# imon.net
KiCad netlist of a schematic drawn in EAGLE
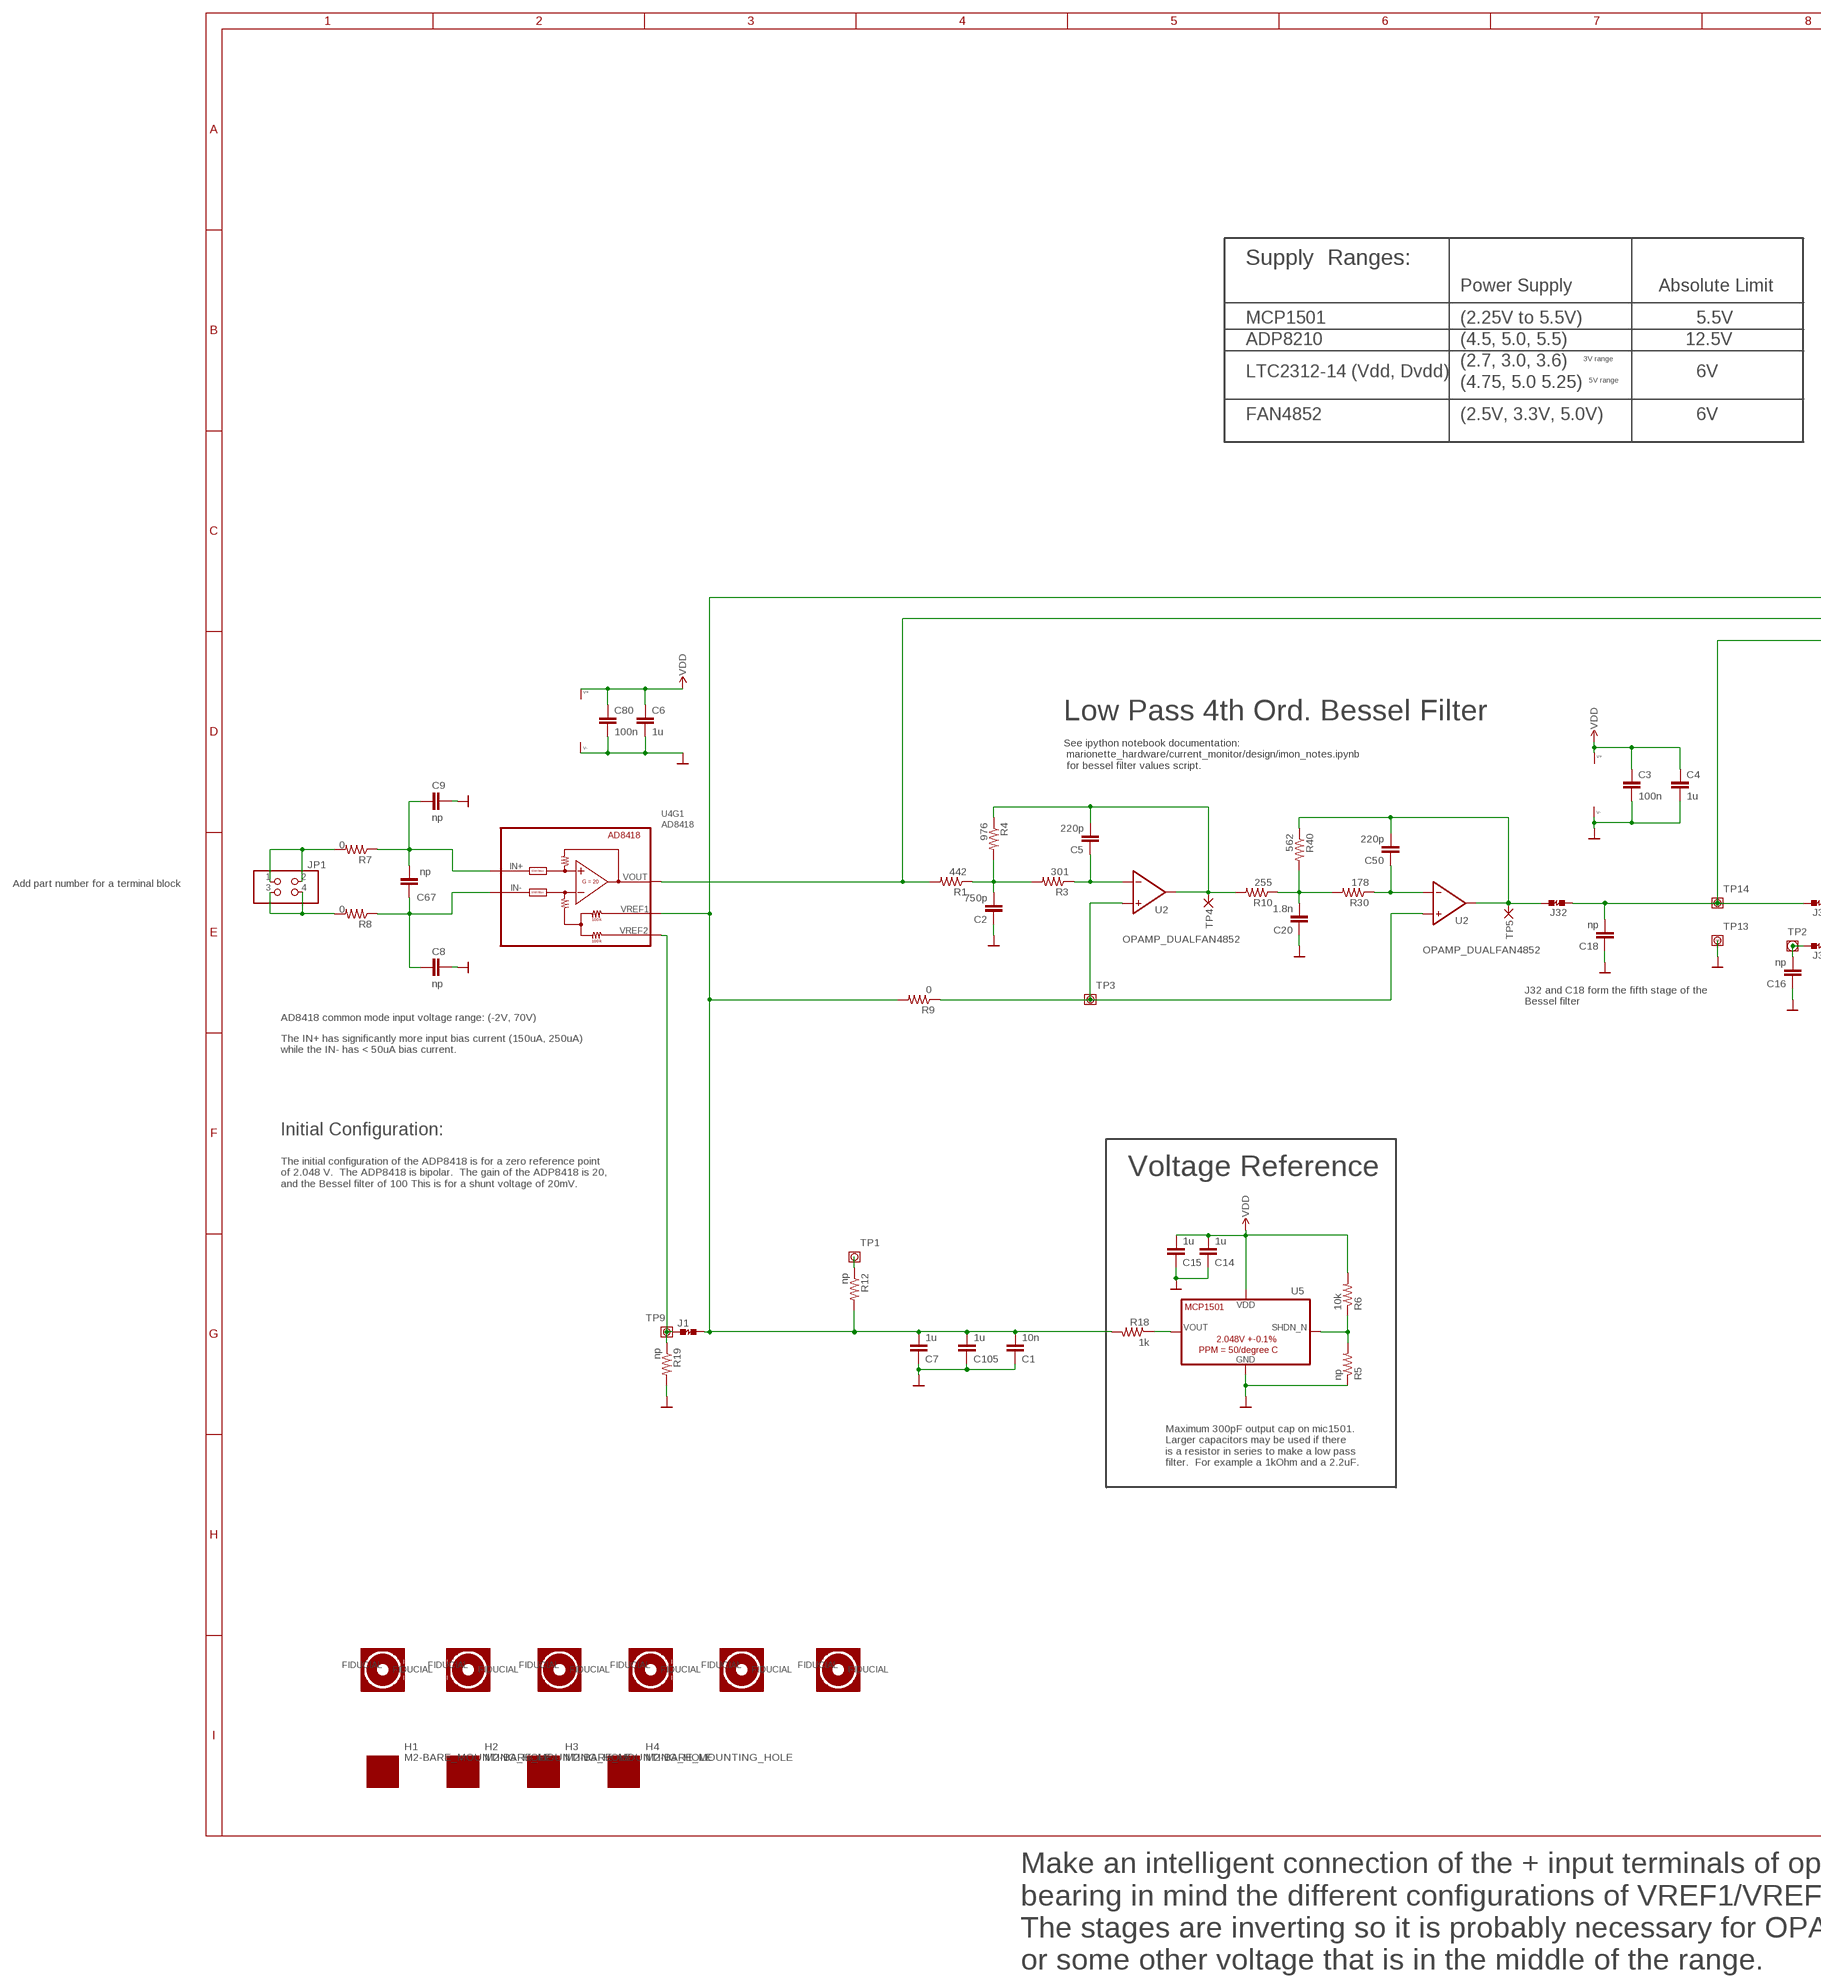
[diagram p0: schematic, sheet 1, part 1 of 2]
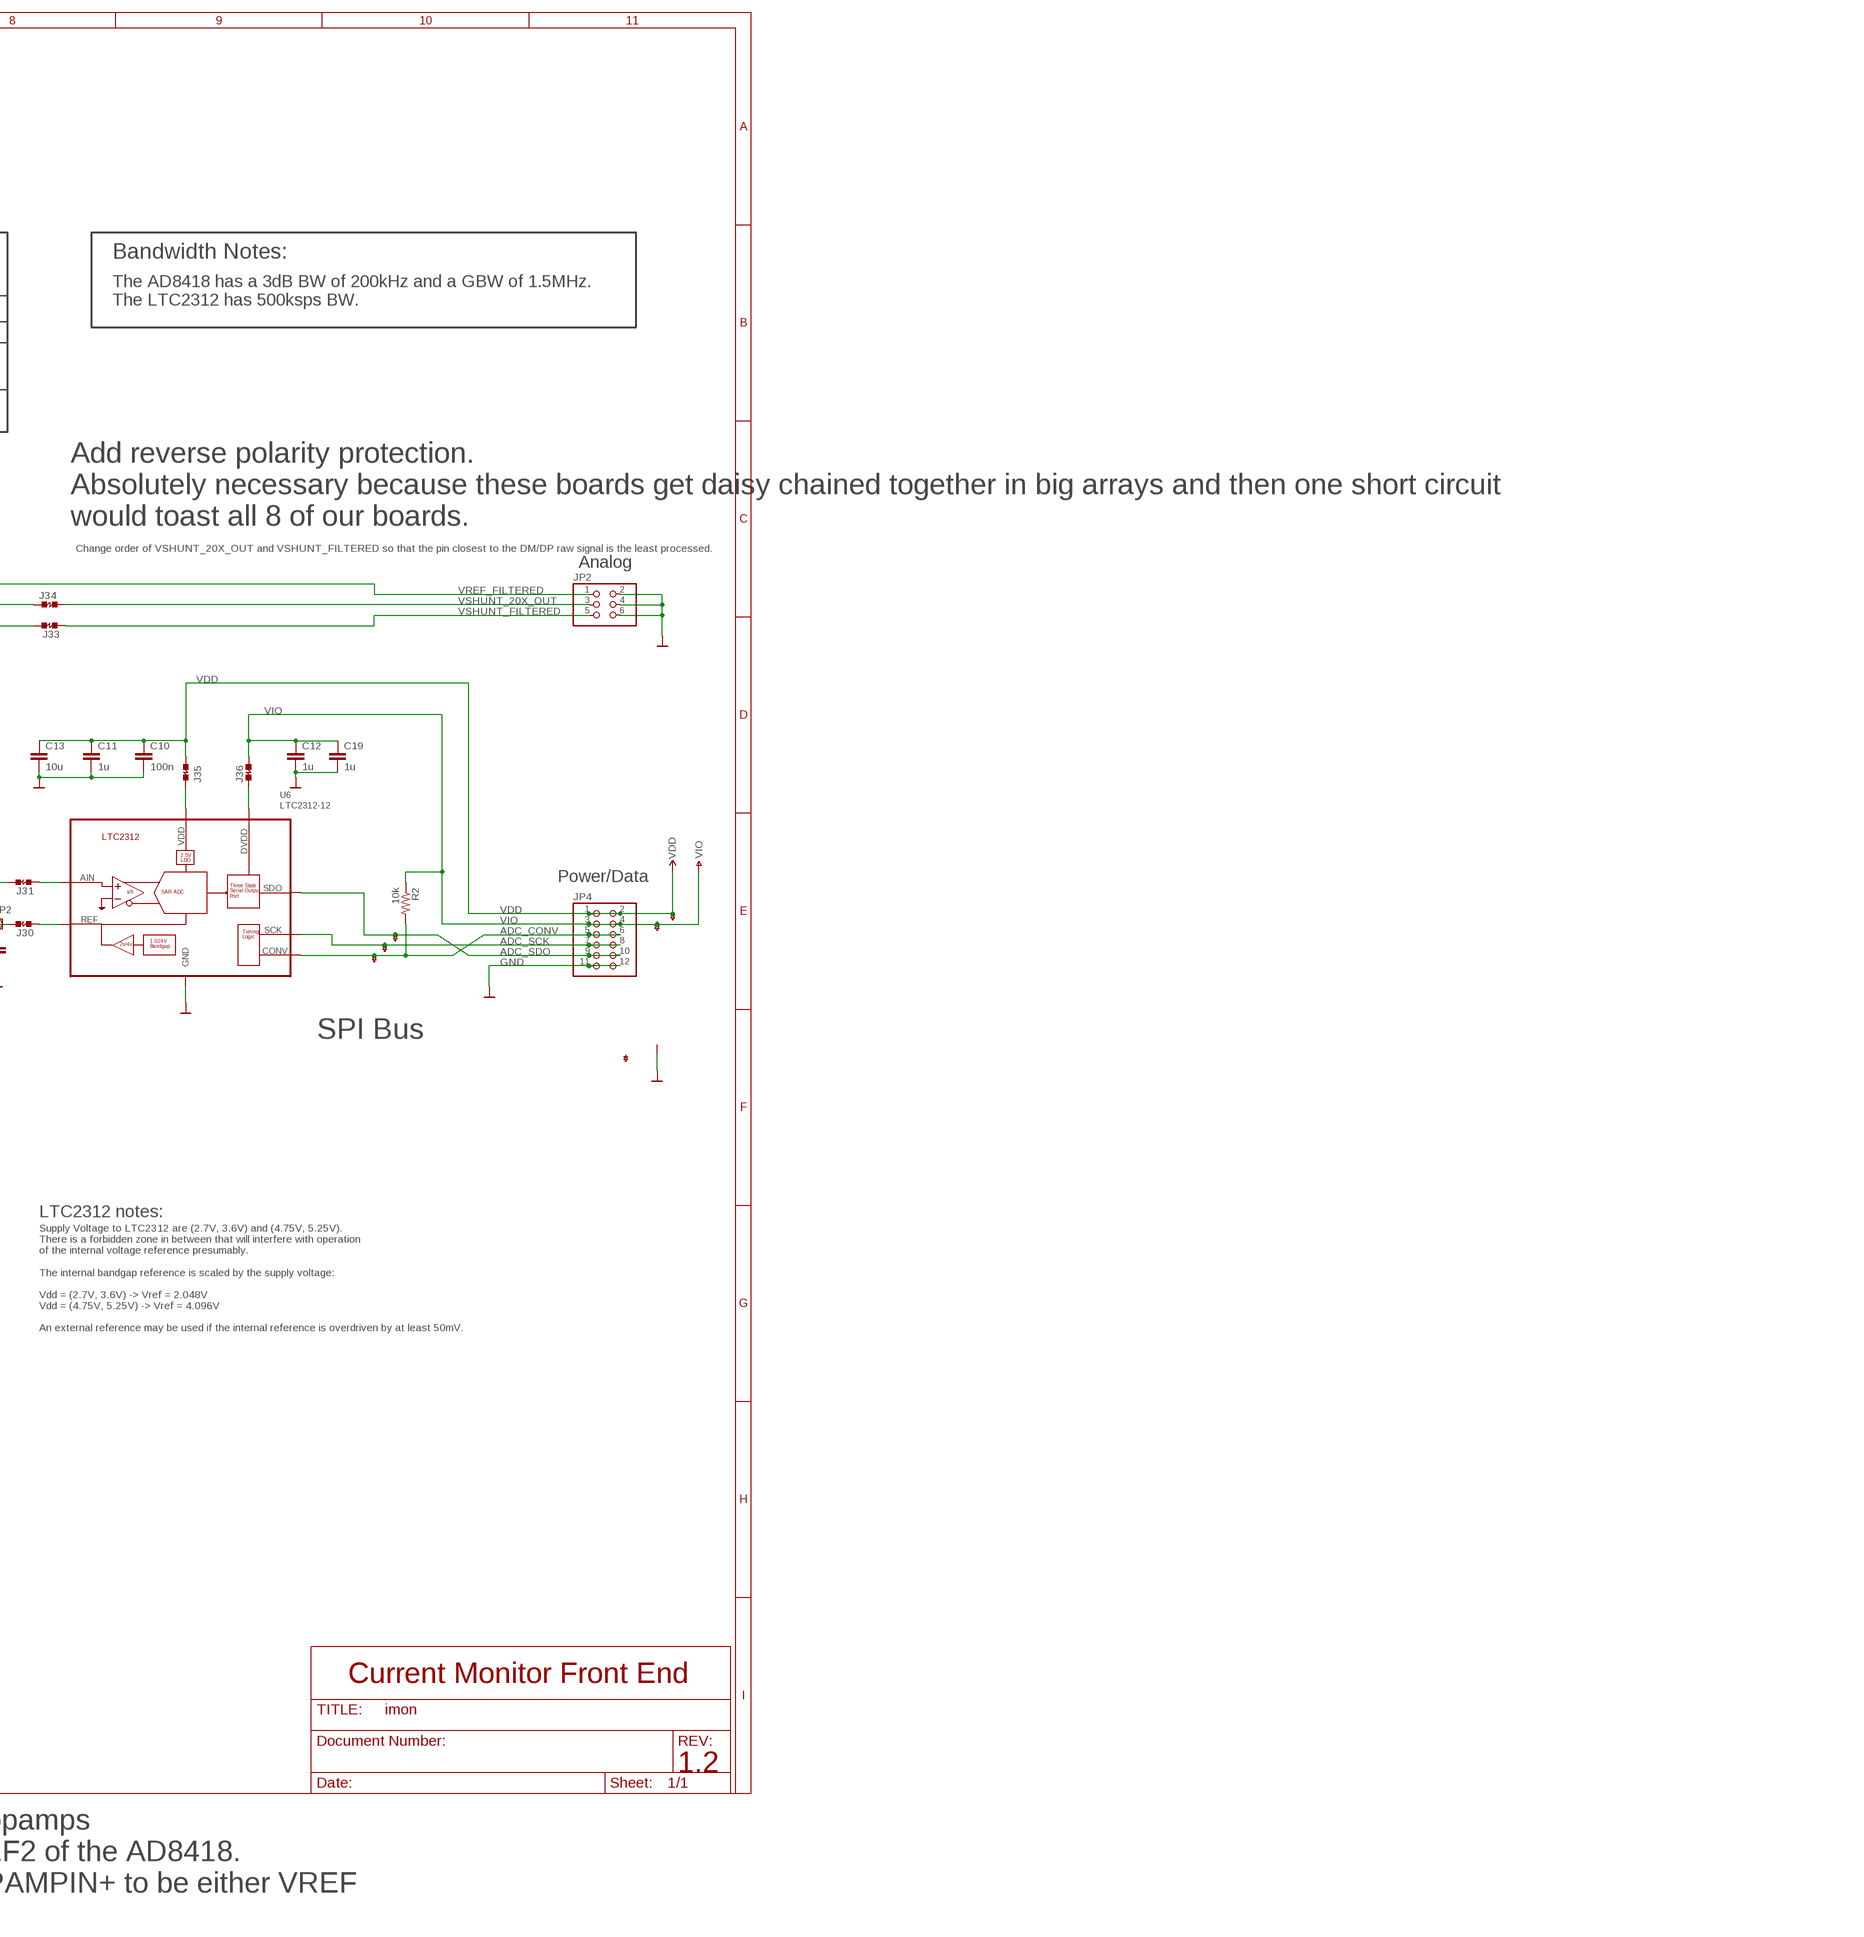
[diagram p1: schematic, sheet 1, part 2 of 2]

(export (version "E")
  (design (tool "Eeschema 10.0.6"))
  (components
    (comp (ref "C1")
      (value "10n")
      (footprint "eagle-import:.0402-B")
      (libsource (lib "eagle-import") (part "C-EU0402-B"))
    )
    (comp (ref "C2")
      (value "750p")
      (footprint "eagle-import:.0402-B")
      (libsource (lib "eagle-import") (part "C-EU0402-B"))
    )
    (comp (ref "C3")
      (value "100n")
      (footprint "eagle-import:.0402-B")
      (libsource (lib "eagle-import") (part "C-EU0402-B"))
    )
    (comp (ref "C4")
      (value "1u")
      (footprint "eagle-import:.0402-B")
      (libsource (lib "eagle-import") (part "C-EU0402-B"))
    )
    (comp (ref "C5")
      (value "220p")
      (footprint "eagle-import:.0402-B")
      (libsource (lib "eagle-import") (part "C-EU0402-B"))
    )
    (comp (ref "C6")
      (value "1u")
      (footprint "eagle-import:.0402-B")
      (libsource (lib "eagle-import") (part "C-EU0402-B"))
    )
    (comp (ref "C7")
      (value "1u")
      (footprint "eagle-import:.0402-B")
      (libsource (lib "eagle-import") (part "C-EU0402-B"))
    )
    (comp (ref "C8")
      (value "np")
      (footprint "eagle-import:.0805-A-NOSILK")
      (libsource (lib "eagle-import") (part "C-EU0805-A-NOSILK"))
    )
    (comp (ref "C9")
      (value "np")
      (footprint "eagle-import:.0805-A-NOSILK")
      (libsource (lib "eagle-import") (part "C-EU0805-A-NOSILK"))
    )
    (comp (ref "C10")
      (value "100n")
      (footprint "eagle-import:.0402-B")
      (libsource (lib "eagle-import") (part "C-EU0402-B"))
    )
    (comp (ref "C11")
      (value "1u")
      (footprint "eagle-import:.0402-B")
      (libsource (lib "eagle-import") (part "C-EU0402-B"))
    )
    (comp (ref "C12")
      (value "1u")
      (footprint "eagle-import:.0402-B")
      (libsource (lib "eagle-import") (part "C-EU0402-B"))
    )
    (comp (ref "C13")
      (value "10u")
      (footprint "eagle-import:.0805-B")
      (libsource (lib "eagle-import") (part "C-EU0805-B"))
    )
    (comp (ref "C14")
      (value "1u")
      (footprint "eagle-import:.0402-B")
      (libsource (lib "eagle-import") (part "C-EU0402-B"))
    )
    (comp (ref "C15")
      (value "1u")
      (footprint "eagle-import:.0402-B")
      (libsource (lib "eagle-import") (part "C-EU0402-B"))
    )
    (comp (ref "C16")
      (value "np")
      (footprint "eagle-import:.0402-B")
      (libsource (lib "eagle-import") (part "C-EU0402-B"))
    )
    (comp (ref "C18")
      (value "np")
      (footprint "eagle-import:.0402-B")
      (libsource (lib "eagle-import") (part "C-EU0402-B"))
    )
    (comp (ref "C19")
      (value "1u")
      (footprint "eagle-import:.0402-B")
      (libsource (lib "eagle-import") (part "C-EU0402-B"))
    )
    (comp (ref "C20")
      (value "1.8n")
      (footprint "eagle-import:.0402-B")
      (libsource (lib "eagle-import") (part "C-EU0402-B"))
    )
    (comp (ref "C50")
      (value "220p")
      (footprint "eagle-import:.0402-B")
      (libsource (lib "eagle-import") (part "C-EU0402-B"))
    )
    (comp (ref "C67")
      (value "np")
      (footprint "eagle-import:1206-0402")
      (libsource (lib "eagle-import") (part "C-EU1206-0402"))
    )
    (comp (ref "C80")
      (value "100n")
      (footprint "eagle-import:.0402-B")
      (libsource (lib "eagle-import") (part "C-EU0402-B"))
    )
    (comp (ref "C105")
      (value "1u")
      (footprint "eagle-import:.0402-B")
      (libsource (lib "eagle-import") (part "C-EU0402-B"))
    )
    (comp (ref "D1")
      (value "ESD8006-ESD8006")
      (footprint "eagle-import:UDFN-8-3.3X1.0_6MIL")
      (libsource (lib "eagle-import") (part "ESD8006-ESD8006"))
    )
    (comp (ref "FIDUCIAL1")
      (value "FIDUCIAL-1.0X2.5")
      (footprint "eagle-import:FIDUCIAL-1.0X2.5")
      (libsource (lib "eagle-import") (part "FIDUCIAL-1.0X2.5"))
    )
    (comp (ref "FIDUCIAL2")
      (value "FIDUCIAL-1.0X2.5")
      (footprint "eagle-import:FIDUCIAL-1.0X2.5")
      (libsource (lib "eagle-import") (part "FIDUCIAL-1.0X2.5"))
    )
    (comp (ref "FIDUCIAL3")
      (value "FIDUCIAL-1.0X2.5")
      (footprint "eagle-import:FIDUCIAL-1.0X2.5")
      (libsource (lib "eagle-import") (part "FIDUCIAL-1.0X2.5"))
    )
    (comp (ref "FIDUCIAL4")
      (value "FIDUCIAL-1.0X2.5")
      (footprint "eagle-import:FIDUCIAL-1.0X2.5")
      (libsource (lib "eagle-import") (part "FIDUCIAL-1.0X2.5"))
    )
    (comp (ref "FIDUCIAL5")
      (value "FIDUCIAL-1.0X2.5")
      (footprint "eagle-import:FIDUCIAL-1.0X2.5")
      (libsource (lib "eagle-import") (part "FIDUCIAL-1.0X2.5"))
    )
    (comp (ref "FIDUCIAL6")
      (value "FIDUCIAL-1.0X2.5")
      (footprint "eagle-import:FIDUCIAL-1.0X2.5")
      (libsource (lib "eagle-import") (part "FIDUCIAL-1.0X2.5"))
    )
    (comp (ref "H1")
      (value "M2-BARE_MOUNTING_HOLE")
      (footprint "eagle-import:M2-BARE_MOUNTING_HOLE")
      (libsource (lib "eagle-import") (part "M2-BARE_MOUNTING_HOLE"))
    )
    (comp (ref "H2")
      (value "M2-BARE_MOUNTING_HOLE")
      (footprint "eagle-import:M2-BARE_MOUNTING_HOLE")
      (libsource (lib "eagle-import") (part "M2-BARE_MOUNTING_HOLE"))
    )
    (comp (ref "H3")
      (value "M2-BARE_MOUNTING_HOLE")
      (footprint "eagle-import:M2-BARE_MOUNTING_HOLE")
      (libsource (lib "eagle-import") (part "M2-BARE_MOUNTING_HOLE"))
    )
    (comp (ref "H4")
      (value "M2-BARE_MOUNTING_HOLE")
      (footprint "eagle-import:M2-BARE_MOUNTING_HOLE")
      (libsource (lib "eagle-import") (part "M2-BARE_MOUNTING_HOLE"))
    )
    (comp (ref "J1")
      (value "JUMPER-SHORTED-CUTTABLE-E0402-0.3MM")
      (footprint "eagle-import:JUMPER-SHORTED-CUTTABLE-E0402-0.3MM")
      (libsource (lib "eagle-import") (part "JUMPER-SHORTED-CUTTABLE-E0402-0.3MM"))
    )
    (comp (ref "J30")
      (value "JUMPER-SHORTED-CUTTABLE-E0402-0.3MM")
      (footprint "eagle-import:JUMPER-SHORTED-CUTTABLE-E0402-0.3MM")
      (libsource (lib "eagle-import") (part "JUMPER-SHORTED-CUTTABLE-E0402-0.3MM"))
    )
    (comp (ref "J31")
      (value "JUMPER-SHORTED-CUTTABLE-E0402-0.3MM")
      (footprint "eagle-import:JUMPER-SHORTED-CUTTABLE-E0402-0.3MM")
      (libsource (lib "eagle-import") (part "JUMPER-SHORTED-CUTTABLE-E0402-0.3MM"))
    )
    (comp (ref "J32")
      (value "JUMPER-SHORTED-CUTTABLE-E0402-0.3MM")
      (footprint "eagle-import:JUMPER-SHORTED-CUTTABLE-E0402-0.3MM")
      (libsource (lib "eagle-import") (part "JUMPER-SHORTED-CUTTABLE-E0402-0.3MM"))
    )
    (comp (ref "J33")
      (value "JUMPER-SHORTED-CUTTABLE-E0402-0.3MM")
      (footprint "eagle-import:JUMPER-SHORTED-CUTTABLE-E0402-0.3MM")
      (libsource (lib "eagle-import") (part "JUMPER-SHORTED-CUTTABLE-E0402-0.3MM"))
    )
    (comp (ref "J34")
      (value "JUMPER-SHORTED-CUTTABLE-E0402-0.3MM")
      (footprint "eagle-import:JUMPER-SHORTED-CUTTABLE-E0402-0.3MM")
      (libsource (lib "eagle-import") (part "JUMPER-SHORTED-CUTTABLE-E0402-0.3MM"))
    )
    (comp (ref "J35")
      (value "JUMPER-SHORTED-CUTTABLE-E0603-0.8MM")
      (footprint "eagle-import:JUMPER-SHORTED-CUTTABLE-E0603-0.8MM")
      (libsource (lib "eagle-import") (part "JUMPER-SHORTED-CUTTABLE-E0603-0.8MM"))
    )
    (comp (ref "J36")
      (value "JUMPER-SHORTED-CUTTABLE-E0603-0.8MM")
      (footprint "eagle-import:JUMPER-SHORTED-CUTTABLE-E0603-0.8MM")
      (libsource (lib "eagle-import") (part "JUMPER-SHORTED-CUTTABLE-E0603-0.8MM"))
    )
    (comp (ref "JP1")
      (value "PINHD-2X2")
      (footprint "eagle-import:2X02")
      (libsource (lib "eagle-import") (part "PINHD-2X2"))
    )
    (comp (ref "JP2")
      (value "PINHD-2X3")
      (footprint "eagle-import:2X03")
      (libsource (lib "eagle-import") (part "PINHD-2X3"))
    )
    (comp (ref "JP4")
      (value "PINHD-2X6/90")
      (footprint "eagle-import:2X06_90")
      (libsource (lib "eagle-import") (part "PINHD-2X6/90"))
    )
    (comp (ref "R1")
      (value "442")
      (footprint "eagle-import:.0402-B")
      (libsource (lib "eagle-import") (part "R-US_0402-B"))
    )
    (comp (ref "R2")
      (value "10k")
      (footprint "eagle-import:.0402-B")
      (libsource (lib "eagle-import") (part "R-US_0402-B"))
    )
    (comp (ref "R3")
      (value "301")
      (footprint "eagle-import:.0402-B")
      (libsource (lib "eagle-import") (part "R-US_0402-B"))
    )
    (comp (ref "R4")
      (value "976")
      (footprint "eagle-import:.0402-B")
      (libsource (lib "eagle-import") (part "R-US_0402-B"))
    )
    (comp (ref "R5")
      (value "np")
      (footprint "eagle-import:.0402-B")
      (libsource (lib "eagle-import") (part "R-US_0402-B"))
    )
    (comp (ref "R6")
      (value "10k")
      (footprint "eagle-import:.0402-B")
      (libsource (lib "eagle-import") (part "R-US_0402-B"))
    )
    (comp (ref "R7")
      (value "0")
      (footprint "eagle-import:1206-0402")
      (libsource (lib "eagle-import") (part "R-US_1206-0402"))
    )
    (comp (ref "R8")
      (value "0")
      (footprint "eagle-import:1206-0402")
      (libsource (lib "eagle-import") (part "R-US_1206-0402"))
    )
    (comp (ref "R9")
      (value "0")
      (footprint "eagle-import:.0402-B")
      (libsource (lib "eagle-import") (part "R-US_0402-B"))
    )
    (comp (ref "R10")
      (value "255")
      (footprint "eagle-import:.0402-B")
      (libsource (lib "eagle-import") (part "R-US_0402-B"))
    )
    (comp (ref "R12")
      (value "np")
      (footprint "eagle-import:.0402-B")
      (libsource (lib "eagle-import") (part "R-US_0402-B"))
    )
    (comp (ref "R18")
      (value "1k")
      (footprint "eagle-import:.0402-B")
      (libsource (lib "eagle-import") (part "R-US_0402-B"))
    )
    (comp (ref "R19")
      (value "np")
      (footprint "eagle-import:.0402-B")
      (libsource (lib "eagle-import") (part "R-US_0402-B"))
    )
    (comp (ref "R30")
      (value "178")
      (footprint "eagle-import:.0402-B")
      (libsource (lib "eagle-import") (part "R-US_0402-B"))
    )
    (comp (ref "R40")
      (value "562")
      (footprint "eagle-import:.0402-B")
      (libsource (lib "eagle-import") (part "R-US_0402-B"))
    )
    (comp (ref "TP1")
      (value "PAD+VIA_0.25MM")
      (footprint "eagle-import:PAD+VIA_0.25MM")
      (libsource (lib "eagle-import") (part "PAD+VIA_0.25MM"))
    )
    (comp (ref "TP2")
      (value "PAD+VIA_0.6MM")
      (footprint "eagle-import:PAD+VIA_0.6MM")
      (libsource (lib "eagle-import") (part "PAD+VIA_0.6MM"))
    )
    (comp (ref "TP3")
      (value "PAD+VIA_0.3302MM")
      (footprint "eagle-import:PAD+VIA_0.3302MM")
      (libsource (lib "eagle-import") (part "PAD+VIA_0.3302MM"))
    )
    (comp (ref "TP4")
      (value "PAD+X-1.0-NO_CREAM+SILK")
      (footprint "eagle-import:PAD-ROUND-1.0-NOCREAM+SILK")
      (libsource (lib "eagle-import") (part "PAD+X-1.0-NO_CREAM+SILK"))
    )
    (comp (ref "TP5")
      (value "PAD+X-1.0-NO_CREAM+SILK")
      (footprint "eagle-import:PAD-ROUND-1.0-NOCREAM+SILK")
      (libsource (lib "eagle-import") (part "PAD+X-1.0-NO_CREAM+SILK"))
    )
    (comp (ref "TP9")
      (value "PAD+VIA_0.25MM")
      (footprint "eagle-import:PAD+VIA_0.25MM")
      (libsource (lib "eagle-import") (part "PAD+VIA_0.25MM"))
    )
    (comp (ref "TP13")
      (value "PAD+VIA_GND_0.25MM")
      (footprint "eagle-import:PAD+GND_VIA_0.25MM")
      (libsource (lib "eagle-import") (part "PAD+VIA_GND_0.25MM"))
    )
    (comp (ref "TP14")
      (value "PAD+VIA_0.25MM")
      (footprint "eagle-import:PAD+VIA_0.25MM")
      (libsource (lib "eagle-import") (part "PAD+VIA_0.25MM"))
    )
    (comp (ref "U2")
      (value "OPAMP_DUALFAN4852")
      (footprint "eagle-import:MSOP-8")
      (fields (field (name "DPN") "FAN4852IMU8XCT-ND  "))
      (libsource (lib "eagle-import") (part "OPAMP_DUALFAN4852"))
    )
    (comp (ref "U4")
      (value "AD8418")
      (footprint "eagle-import:SOIC-8_BETTER_TOE")
      (fields (field (name "DPN") "AD8418WBRZ-ND"))
      (libsource (lib "eagle-import") (part "AD8418"))
    )
    (comp (ref "U5")
      (value "MCP1501\"")
      (footprint "eagle-import:SOT23-6")
      (fields (field (name "PPM") "50/degree C") (field (name "VREF") "2.048V +-0.1%"))
      (libsource (lib "eagle-import") (part "MCP1501{dblquote}"))
    )
    (comp (ref "U6")
      (value "LTC2312-12")
      (footprint "eagle-import:TSOT23-8")
      (libsource (lib "eagle-import") (part "LTC2312-12"))
    )
  )
  (nets
    (net (code "1") (name "/ADC_CONV") (class "Default")
      (node (ref "D1") (pin "4") (pinfunction "CATHODE_4") (pintype "bidirectional"))
      (node (ref "JP4") (pin "5") (pinfunction "5_5") (pintype "passive"))
      (node (ref "JP4") (pin "6") (pinfunction "6_6") (pintype "passive"))
      (node (ref "R2") (pin "2") (pinfunction "2_2") (pintype "passive"))
      (node (ref "U6") (pin "8") (pinfunction "CONV_8") (pintype "bidirectional"))
    )
    (net (code "2") (name "/ADC_SCK") (class "Default")
      (node (ref "D1") (pin "2") (pinfunction "CATHODE_2") (pintype "bidirectional"))
      (node (ref "JP4") (pin "7") (pinfunction "7_7") (pintype "passive"))
      (node (ref "JP4") (pin "8") (pinfunction "8_8") (pintype "passive"))
      (node (ref "U6") (pin "7") (pinfunction "SCK_7") (pintype "bidirectional"))
    )
    (net (code "3") (name "/ADC_SDO") (class "Default")
      (node (ref "D1") (pin "1") (pinfunction "CATHODE_1") (pintype "bidirectional"))
      (node (ref "JP4") (pin "10") (pinfunction "10_10") (pintype "passive"))
      (node (ref "JP4") (pin "9") (pinfunction "9_9") (pintype "passive"))
      (node (ref "U6") (pin "6") (pinfunction "SDO_6") (pintype "output"))
    )
    (net (code "4") (name "/VREF_FILTERED") (class "Default")
      (node (ref "C1") (pin "2") (pinfunction "2_2") (pintype "passive"))
      (node (ref "C105") (pin "2") (pinfunction "2_2") (pintype "passive"))
      (node (ref "C7") (pin "2") (pinfunction "2_2") (pintype "passive"))
      (node (ref "J1") (pin "2") (pinfunction "2_2") (pintype "passive"))
      (node (ref "JP2") (pin "1") (pinfunction "1_1") (pintype "passive"))
      (node (ref "R12") (pin "2") (pinfunction "2_2") (pintype "passive"))
      (node (ref "R18") (pin "2") (pinfunction "2_2") (pintype "passive"))
      (node (ref "R9") (pin "2") (pinfunction "2_2") (pintype "passive"))
      (node (ref "U4") (pin "7") (pinfunction "VREF1_7") (pintype "input"))
    )
    (net (code "5") (name "/VSHUNT_20X_OUT") (class "Default")
      (node (ref "J34") (pin "2") (pinfunction "2_2") (pintype "passive"))
      (node (ref "JP2") (pin "3") (pinfunction "3_3") (pintype "passive"))
    )
    (net (code "6") (name "/VSHUNT_FILTERED") (class "Default")
      (node (ref "J33") (pin "1") (pinfunction "1_1") (pintype "passive"))
      (node (ref "JP2") (pin "5") (pinfunction "5_5") (pintype "passive"))
    )
    (net (code "7") (name "GND") (class "Default")
      (node (ref "C1") (pin "1") (pinfunction "1_1") (pintype "passive"))
      (node (ref "C10") (pin "2") (pinfunction "2_2") (pintype "passive"))
      (node (ref "C105") (pin "1") (pinfunction "1_1") (pintype "passive"))
      (node (ref "C11") (pin "2") (pinfunction "2_2") (pintype "passive"))
      (node (ref "C12") (pin "2") (pinfunction "2_2") (pintype "passive"))
      (node (ref "C13") (pin "2") (pinfunction "2_2") (pintype "passive"))
      (node (ref "C14") (pin "1") (pinfunction "1_1") (pintype "passive"))
      (node (ref "C15") (pin "1") (pinfunction "1_1") (pintype "passive"))
      (node (ref "C16") (pin "1") (pinfunction "1_1") (pintype "passive"))
      (node (ref "C18") (pin "1") (pinfunction "1_1") (pintype "passive"))
      (node (ref "C19") (pin "2") (pinfunction "2_2") (pintype "passive"))
      (node (ref "C2") (pin "1") (pinfunction "1_1") (pintype "passive"))
      (node (ref "C20") (pin "1") (pinfunction "1_1") (pintype "passive"))
      (node (ref "C3") (pin "2") (pinfunction "2_2") (pintype "passive"))
      (node (ref "C4") (pin "2") (pinfunction "2_2") (pintype "passive"))
      (node (ref "C6") (pin "2") (pinfunction "2_2") (pintype "passive"))
      (node (ref "C7") (pin "1") (pinfunction "1_1") (pintype "passive"))
      (node (ref "C8") (pin "1") (pinfunction "1_1") (pintype "passive"))
      (node (ref "C80") (pin "2") (pinfunction "2_2") (pintype "passive"))
      (node (ref "C9") (pin "1") (pinfunction "1_1") (pintype "passive"))
      (node (ref "D1") (pin "10") (pinfunction "PIN_10") (pintype "power_in"))
      (node (ref "D1") (pin "3") (pinfunction "PIN_3") (pintype "power_in"))
      (node (ref "D1") (pin "6") (pinfunction "PIN_6") (pintype "power_in"))
      (node (ref "D1") (pin "9") (pinfunction "PIN_9") (pintype "power_in"))
      (node (ref "JP2") (pin "2") (pinfunction "2_2") (pintype "passive"))
      (node (ref "JP2") (pin "4") (pinfunction "4_4") (pintype "passive"))
      (node (ref "JP2") (pin "6") (pinfunction "6_6") (pintype "passive"))
      (node (ref "JP4") (pin "11") (pinfunction "11_11") (pintype "passive"))
      (node (ref "JP4") (pin "12") (pinfunction "12_12") (pintype "passive"))
      (node (ref "R19") (pin "2") (pinfunction "2_2") (pintype "passive"))
      (node (ref "R5") (pin "1") (pinfunction "1_1") (pintype "passive"))
      (node (ref "TP13") (pin "TP") (pinfunction "TP_TP") (pintype "passive"))
      (node (ref "U2") (pin "4") (pinfunction "V-_4") (pintype "power_in"))
      (node (ref "U4") (pin "2") (pinfunction "V-_2") (pintype "power_in"))
      (node (ref "U5") (pin "2") (pinfunction "GND_2") (pintype "power_in"))
      (node (ref "U5") (pin "3") (pinfunction "GND_3") (pintype "power_in"))
      (node (ref "U5") (pin "5") (pinfunction "GND_5") (pintype "power_in"))
      (node (ref "U6") (pin "3") (pinfunction "GND_3") (pintype "power_in"))
    )
    (net (code "8") (name "Net-(C2-Pad2)") (class "Default")
      (node (ref "C2") (pin "2") (pinfunction "2_2") (pintype "passive"))
      (node (ref "R1") (pin "1") (pinfunction "1_1") (pintype "passive"))
      (node (ref "R3") (pin "2") (pinfunction "2_2") (pintype "passive"))
      (node (ref "R4") (pin "2") (pinfunction "2_2") (pintype "passive"))
    )
    (net (code "9") (name "Net-(C16-Pad2)") (class "Default")
      (node (ref "C16") (pin "2") (pinfunction "2_2") (pintype "passive"))
      (node (ref "J30") (pin "2") (pinfunction "2_2") (pintype "passive"))
      (node (ref "TP2") (pin "TP") (pinfunction "TP_TP") (pintype "passive"))
    )
    (net (code "10") (name "Net-(C18-Pad2)") (class "Default")
      (node (ref "C18") (pin "2") (pinfunction "2_2") (pintype "passive"))
      (node (ref "J31") (pin "2") (pinfunction "2_2") (pintype "passive"))
      (node (ref "J32") (pin "1") (pinfunction "1_1") (pintype "passive"))
      (node (ref "J33") (pin "2") (pinfunction "2_2") (pintype "passive"))
      (node (ref "TP14") (pin "TP") (pinfunction "TP_TP") (pintype "passive"))
    )
    (net (code "11") (name "Net-(C20-Pad2)") (class "Default")
      (node (ref "C20") (pin "2") (pinfunction "2_2") (pintype "passive"))
      (node (ref "R10") (pin "1") (pinfunction "1_1") (pintype "passive"))
      (node (ref "R30") (pin "2") (pinfunction "2_2") (pintype "passive"))
      (node (ref "R40") (pin "2") (pinfunction "2_2") (pintype "passive"))
    )
    (net (code "12") (name "Net-(JP1-Pad1)") (class "Default")
      (node (ref "JP1") (pin "1") (pinfunction "1_1") (pintype "passive"))
      (node (ref "JP1") (pin "2") (pinfunction "2_2") (pintype "passive"))
      (node (ref "R7") (pin "2") (pinfunction "2_2") (pintype "passive"))
    )
    (net (code "13") (name "Net-(JP1-Pad3)") (class "Default")
      (node (ref "JP1") (pin "3") (pinfunction "3_3") (pintype "passive"))
      (node (ref "JP1") (pin "4") (pinfunction "4_4") (pintype "passive"))
      (node (ref "R8") (pin "2") (pinfunction "2_2") (pintype "passive"))
    )
    (net (code "14") (name "Net-(R12-Pad1)") (class "Default")
      (node (ref "R12") (pin "1") (pinfunction "1_1") (pintype "passive"))
      (node (ref "TP1") (pin "TP") (pinfunction "TP_TP") (pintype "passive"))
    )
    (net (code "15") (name "Net-(TP4-P)") (class "Default")
      (node (ref "C5") (pin "2") (pinfunction "2_2") (pintype "passive"))
      (node (ref "R10") (pin "2") (pinfunction "2_2") (pintype "passive"))
      (node (ref "R4") (pin "1") (pinfunction "1_1") (pintype "passive"))
      (node (ref "TP4") (pin "PAD") (pinfunction "P_PAD") (pintype "passive"))
      (node (ref "U2") (pin "1") (pinfunction "OUT_1") (pintype "output"))
    )
    (net (code "16") (name "Net-(TP5-P)") (class "Default")
      (node (ref "C50") (pin "2") (pinfunction "2_2") (pintype "passive"))
      (node (ref "J32") (pin "2") (pinfunction "2_2") (pintype "passive"))
      (node (ref "R40") (pin "1") (pinfunction "1_1") (pintype "passive"))
      (node (ref "TP5") (pin "PAD") (pinfunction "P_PAD") (pintype "passive"))
      (node (ref "U2") (pin "7") (pinfunction "OUT_7") (pintype "output"))
    )
    (net (code "17") (name "Net-(U2A-+IN)") (class "Default")
      (node (ref "R9") (pin "1") (pinfunction "1_1") (pintype "passive"))
      (node (ref "TP3") (pin "TP") (pinfunction "TP_TP") (pintype "passive"))
      (node (ref "U2") (pin "3") (pinfunction "+IN_3") (pintype "input"))
      (node (ref "U2") (pin "5") (pinfunction "+IN_5") (pintype "input"))
    )
    (net (code "18") (name "Net-(U2A--IN)") (class "Default")
      (node (ref "C5") (pin "1") (pinfunction "1_1") (pintype "passive"))
      (node (ref "R3") (pin "1") (pinfunction "1_1") (pintype "passive"))
      (node (ref "U2") (pin "2") (pinfunction "-IN_2") (pintype "input"))
    )
    (net (code "19") (name "Net-(U2B--IN)") (class "Default")
      (node (ref "C50") (pin "1") (pinfunction "1_1") (pintype "passive"))
      (node (ref "R30") (pin "1") (pinfunction "1_1") (pintype "passive"))
      (node (ref "U2") (pin "6") (pinfunction "-IN_6") (pintype "input"))
    )
    (net (code "20") (name "Net-(U4A-IN+)") (class "Default")
      (node (ref "C67") (pin "2") (pinfunction "2_2") (pintype "passive"))
      (node (ref "C9") (pin "2") (pinfunction "2_2") (pintype "passive"))
      (node (ref "R7") (pin "1") (pinfunction "1_1") (pintype "passive"))
      (node (ref "U4") (pin "8") (pinfunction "IN+_8") (pintype "input"))
    )
    (net (code "21") (name "Net-(U4A-IN-)") (class "Default")
      (node (ref "C67") (pin "1") (pinfunction "1_1") (pintype "passive"))
      (node (ref "C8") (pin "2") (pinfunction "2_2") (pintype "passive"))
      (node (ref "R8") (pin "1") (pinfunction "1_1") (pintype "passive"))
      (node (ref "U4") (pin "1") (pinfunction "IN-_1") (pintype "input"))
    )
    (net (code "22") (name "Net-(U4A-VOUT)") (class "Default")
      (node (ref "J34") (pin "1") (pinfunction "1_1") (pintype "passive"))
      (node (ref "R1") (pin "2") (pinfunction "2_2") (pintype "passive"))
      (node (ref "U4") (pin "5") (pinfunction "VOUT_5") (pintype "output"))
    )
    (net (code "23") (name "Net-(U4A-VREF2)") (class "Default")
      (node (ref "J1") (pin "1") (pinfunction "1_1") (pintype "passive"))
      (node (ref "R19") (pin "1") (pinfunction "1_1") (pintype "passive"))
      (node (ref "TP9") (pin "TP") (pinfunction "TP_TP") (pintype "passive"))
      (node (ref "U4") (pin "3") (pinfunction "VREF2_3") (pintype "input"))
    )
    (net (code "24") (name "Net-(U5-SHDN_N)") (class "Default")
      (node (ref "R5") (pin "2") (pinfunction "2_2") (pintype "passive"))
      (node (ref "R6") (pin "1") (pinfunction "1_1") (pintype "passive"))
      (node (ref "U5") (pin "4") (pinfunction "SHDN_N_4") (pintype "input"))
    )
    (net (code "25") (name "Net-(U5-VOUT)") (class "Default")
      (node (ref "R18") (pin "1") (pinfunction "1_1") (pintype "passive"))
      (node (ref "U5") (pin "1") (pinfunction "VOUT_1") (pintype "output"))
    )
    (net (code "26") (name "Net-(U6-AIN)") (class "Default")
      (node (ref "J31") (pin "1") (pinfunction "1_1") (pintype "passive"))
      (node (ref "U6") (pin "4") (pinfunction "AIN_4") (pintype "input"))
    )
    (net (code "27") (name "Net-(U6-DVDD)") (class "Default")
      (node (ref "J36") (pin "1") (pinfunction "1_1") (pintype "passive"))
      (node (ref "U6") (pin "5") (pinfunction "DVDD_5") (pintype "power_in"))
    )
    (net (code "28") (name "Net-(U6-REF)") (class "Default")
      (node (ref "J30") (pin "1") (pinfunction "1_1") (pintype "passive"))
      (node (ref "U6") (pin "2") (pinfunction "REF_2") (pintype "input"))
    )
    (net (code "29") (name "Net-(U6-VDD)") (class "Default")
      (node (ref "J35") (pin "1") (pinfunction "1_1") (pintype "passive"))
      (node (ref "U6") (pin "1") (pinfunction "VDD_1") (pintype "power_in"))
    )
    (net (code "30") (name "VDD") (class "Default")
      (node (ref "C10") (pin "1") (pinfunction "1_1") (pintype "passive"))
      (node (ref "C11") (pin "1") (pinfunction "1_1") (pintype "passive"))
      (node (ref "C13") (pin "1") (pinfunction "1_1") (pintype "passive"))
      (node (ref "C14") (pin "2") (pinfunction "2_2") (pintype "passive"))
      (node (ref "C15") (pin "2") (pinfunction "2_2") (pintype "passive"))
      (node (ref "C3") (pin "1") (pinfunction "1_1") (pintype "passive"))
      (node (ref "C4") (pin "1") (pinfunction "1_1") (pintype "passive"))
      (node (ref "C6") (pin "1") (pinfunction "1_1") (pintype "passive"))
      (node (ref "C80") (pin "1") (pinfunction "1_1") (pintype "passive"))
      (node (ref "D1") (pin "8") (pinfunction "CATHODE_8") (pintype "bidirectional"))
      (node (ref "J35") (pin "2") (pinfunction "2_2") (pintype "passive"))
      (node (ref "JP4") (pin "1") (pinfunction "1_1") (pintype "passive"))
      (node (ref "JP4") (pin "2") (pinfunction "2_2") (pintype "passive"))
      (node (ref "R6") (pin "2") (pinfunction "2_2") (pintype "passive"))
      (node (ref "U2") (pin "8") (pinfunction "V+_8") (pintype "power_in"))
      (node (ref "U4") (pin "6") (pinfunction "V+_6") (pintype "power_in"))
      (node (ref "U5") (pin "6") (pinfunction "VDD_6") (pintype "power_in"))
    )
    (net (code "31") (name "VIO") (class "Default")
      (node (ref "C12") (pin "1") (pinfunction "1_1") (pintype "passive"))
      (node (ref "C19") (pin "1") (pinfunction "1_1") (pintype "passive"))
      (node (ref "D1") (pin "7") (pinfunction "CATHODE_7") (pintype "bidirectional"))
      (node (ref "J36") (pin "2") (pinfunction "2_2") (pintype "passive"))
      (node (ref "JP4") (pin "3") (pinfunction "3_3") (pintype "passive"))
      (node (ref "JP4") (pin "4") (pinfunction "4_4") (pintype "passive"))
      (node (ref "R2") (pin "1") (pinfunction "1_1") (pintype "passive"))
    )
    (net (code "32") (name "unconnected-(D1D-CATHODE-Pad5)") (class "Default")
      (node (ref "D1") (pin "5") (pinfunction "CATHODE_5") (pintype "bidirectional"))
    )
    (net (code "33") (name "unconnected-(FIDUCIAL1-PadFIDUCIAL)") (class "Default")
      (node (ref "FIDUCIAL1") (pin "FIDUCIAL") (pinfunction "FIDUCIAL_FIDUCIAL") (pintype "no_connect"))
    )
    (net (code "34") (name "unconnected-(FIDUCIAL2-PadFIDUCIAL)") (class "Default")
      (node (ref "FIDUCIAL2") (pin "FIDUCIAL") (pinfunction "FIDUCIAL_FIDUCIAL") (pintype "no_connect"))
    )
    (net (code "35") (name "unconnected-(FIDUCIAL3-PadFIDUCIAL)") (class "Default")
      (node (ref "FIDUCIAL3") (pin "FIDUCIAL") (pinfunction "FIDUCIAL_FIDUCIAL") (pintype "no_connect"))
    )
    (net (code "36") (name "unconnected-(FIDUCIAL4-PadFIDUCIAL)") (class "Default")
      (node (ref "FIDUCIAL4") (pin "FIDUCIAL") (pinfunction "FIDUCIAL_FIDUCIAL") (pintype "no_connect"))
    )
    (net (code "37") (name "unconnected-(FIDUCIAL5-PadFIDUCIAL)") (class "Default")
      (node (ref "FIDUCIAL5") (pin "FIDUCIAL") (pinfunction "FIDUCIAL_FIDUCIAL") (pintype "no_connect"))
    )
    (net (code "38") (name "unconnected-(FIDUCIAL6-PadFIDUCIAL)") (class "Default")
      (node (ref "FIDUCIAL6") (pin "FIDUCIAL") (pinfunction "FIDUCIAL_FIDUCIAL") (pintype "no_connect"))
    )
  )
)
